# dig_ac230.net
KiCad netlist of a schematic drawn in EAGLE
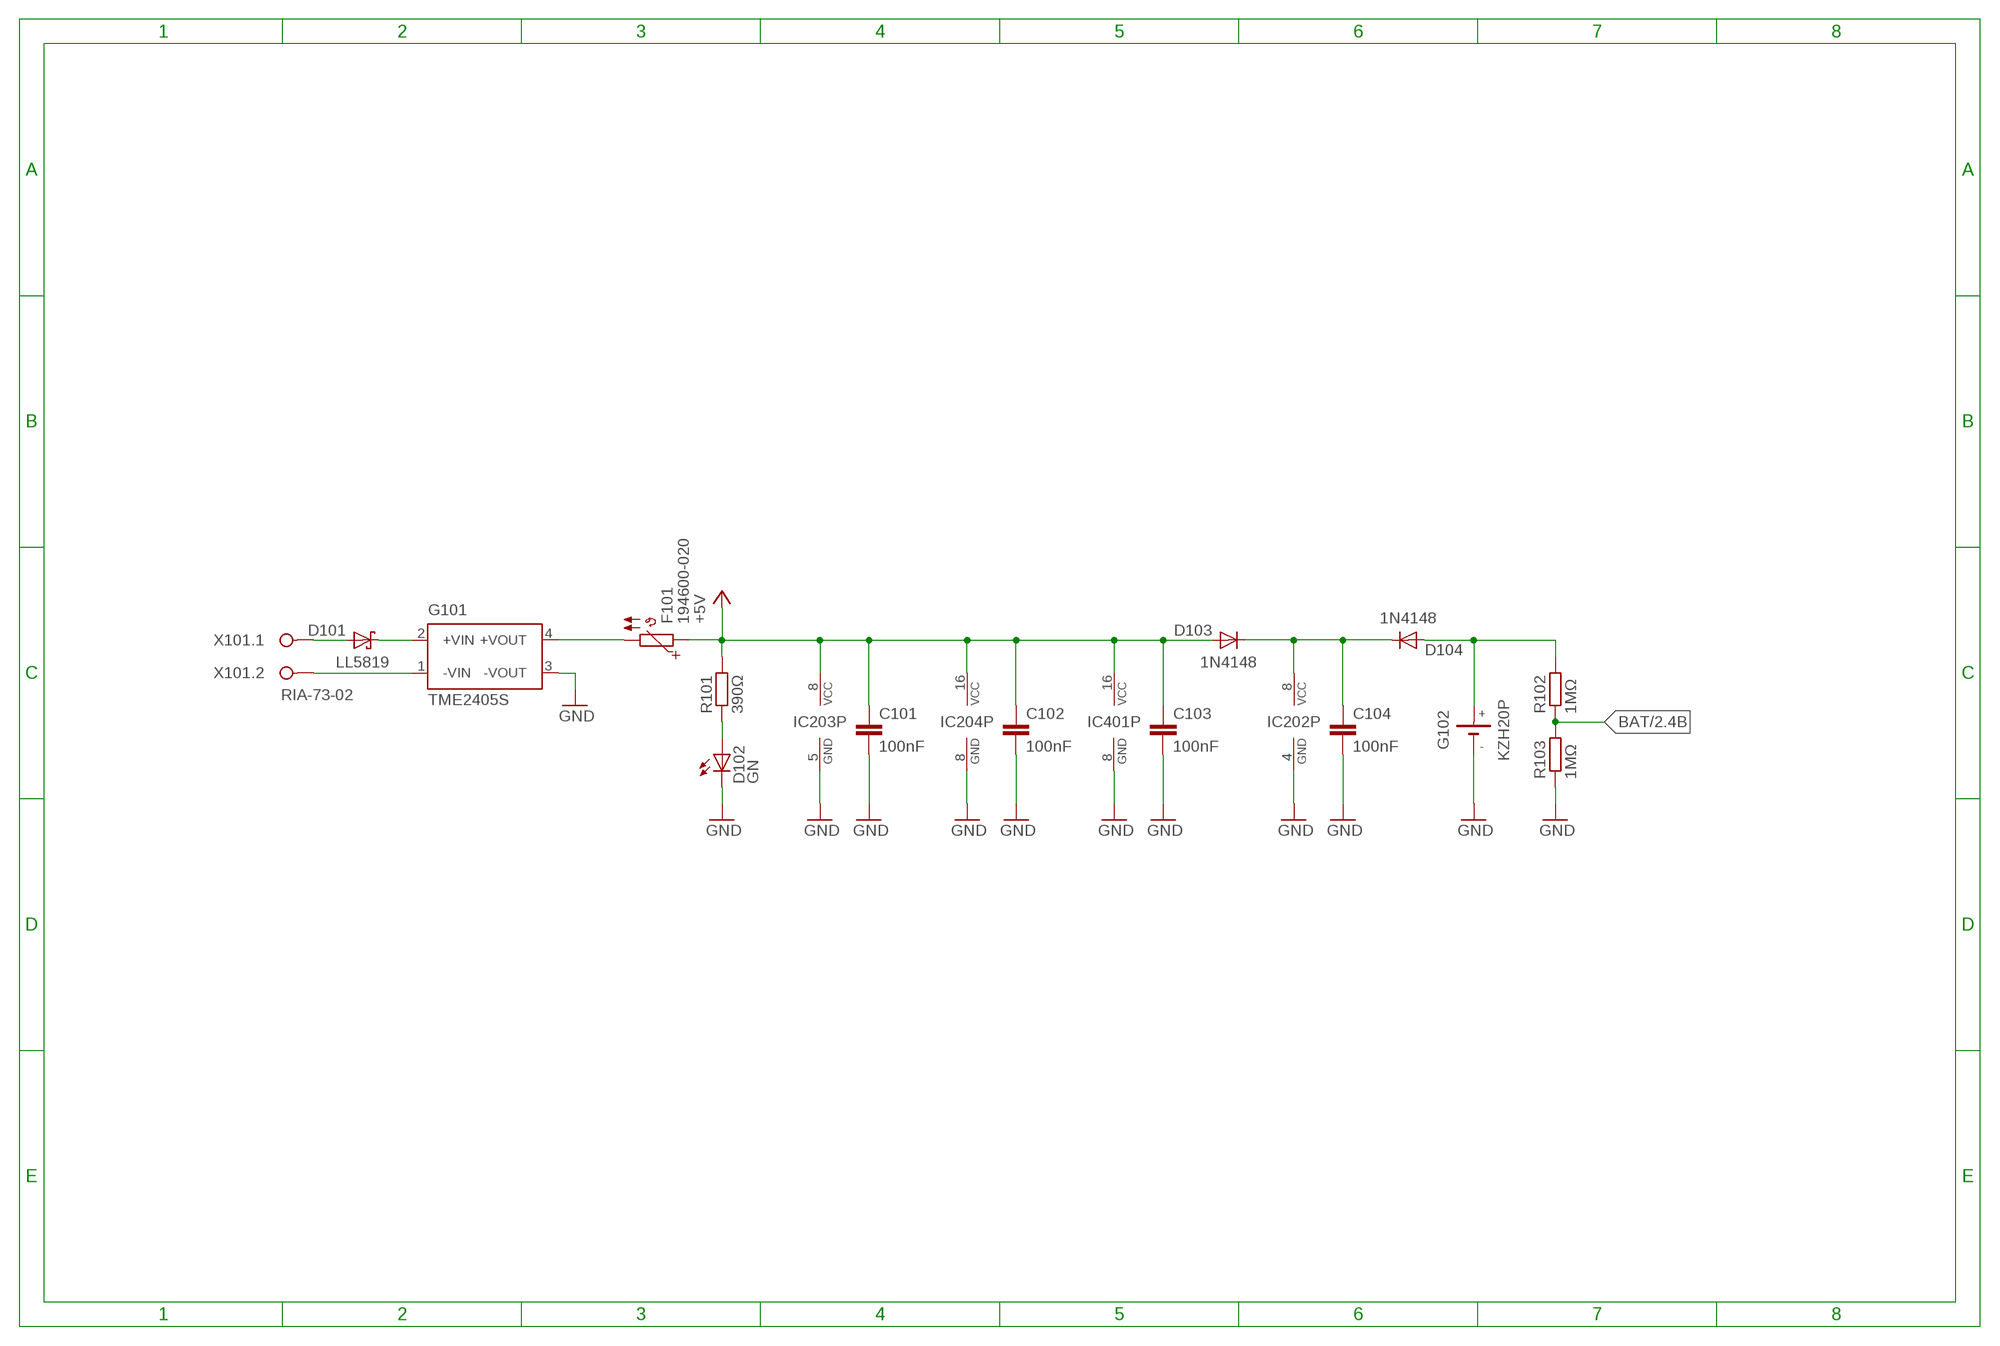
[diagram p0: schematic, sheet 1]
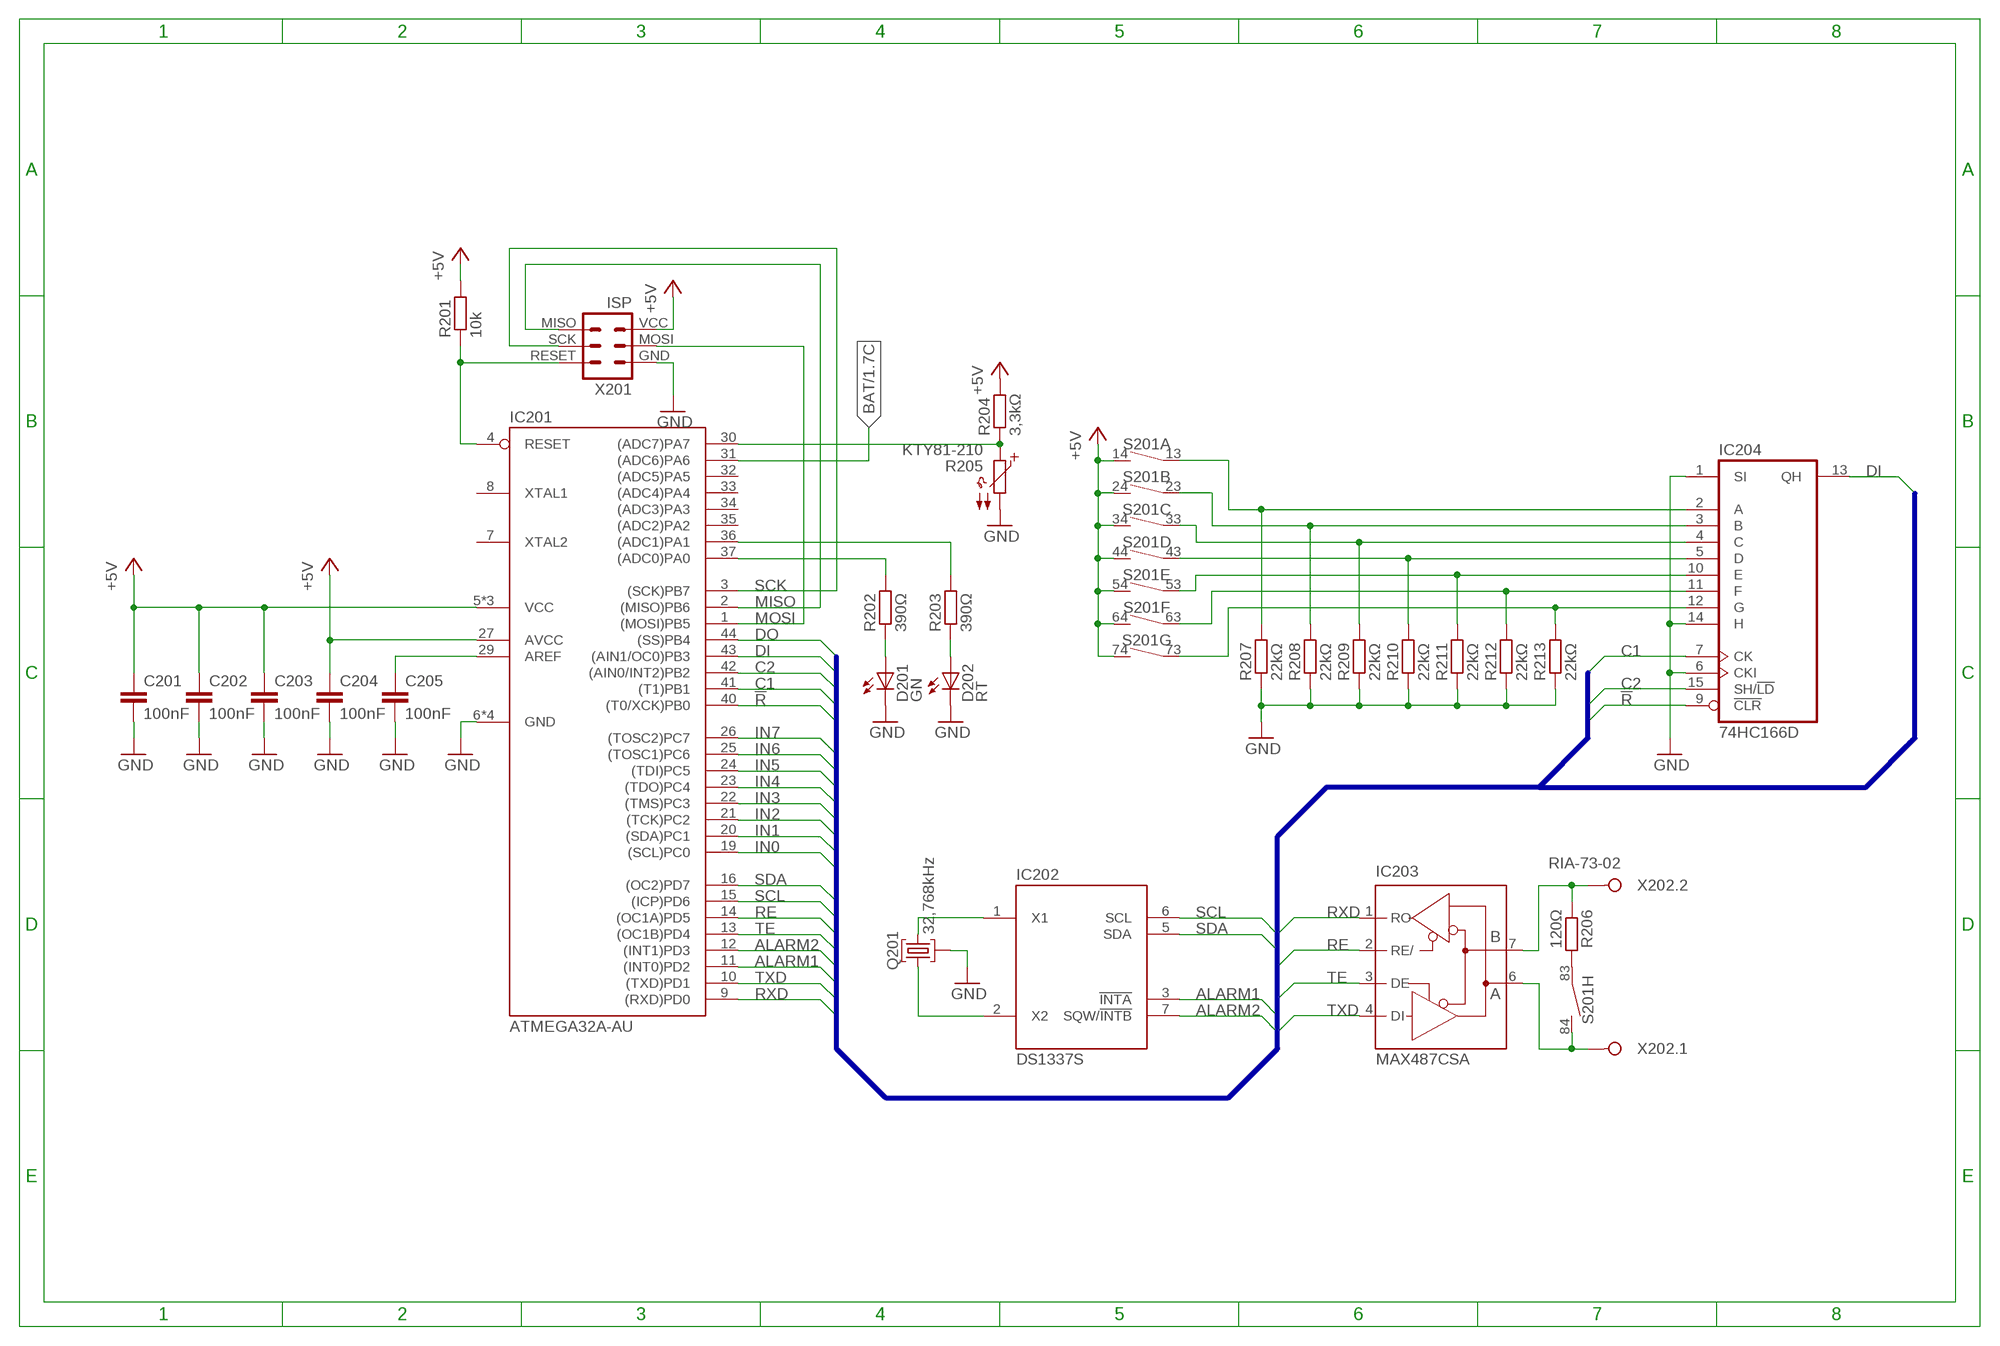
[diagram p1: schematic, sheet 2]
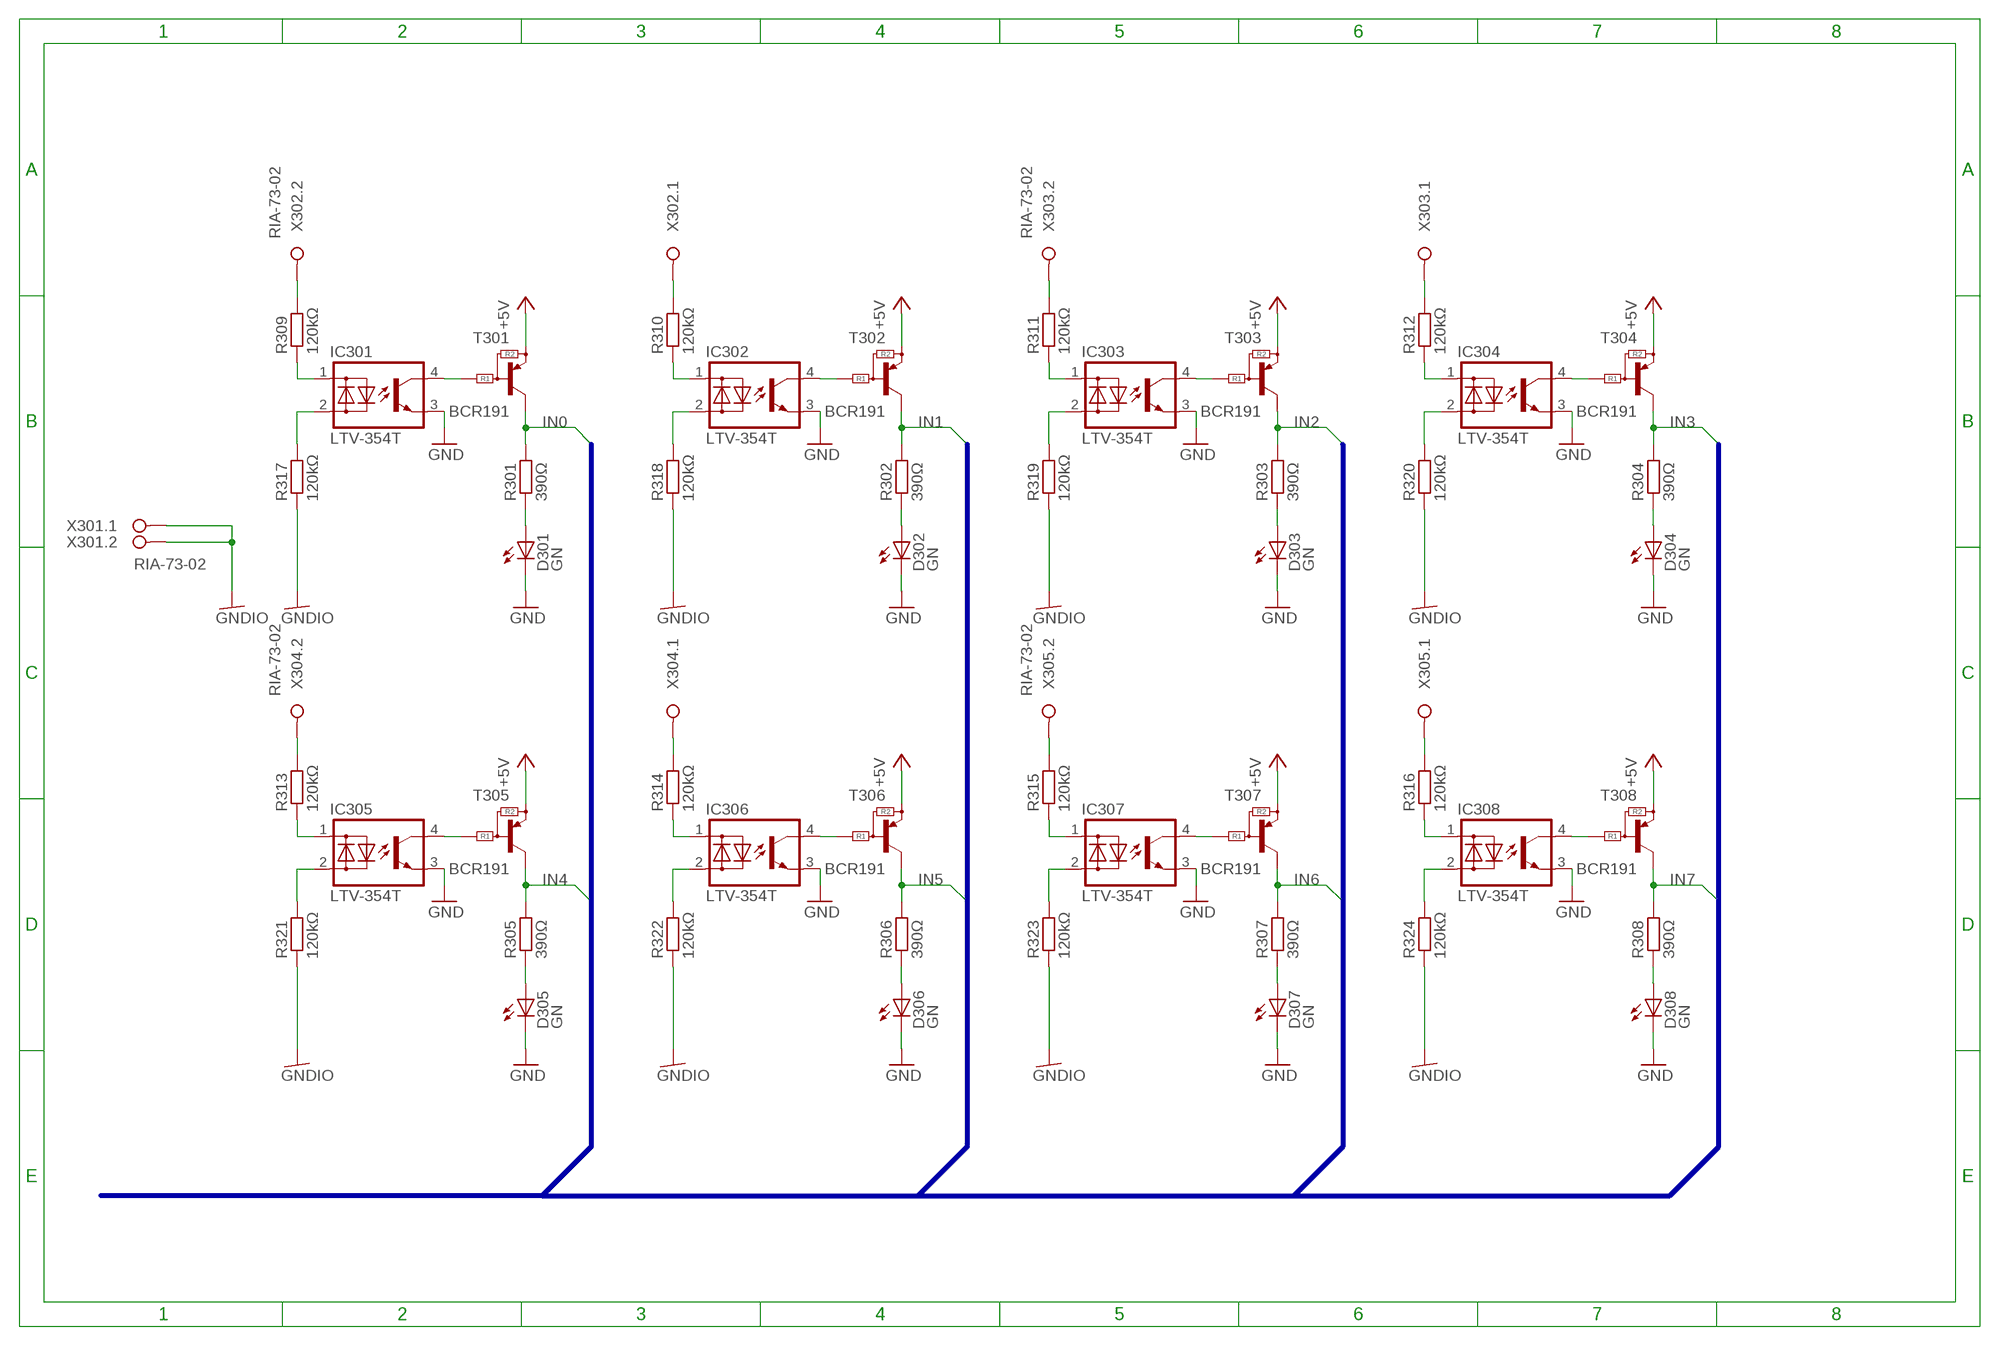
[diagram p2: schematic, sheet 3]
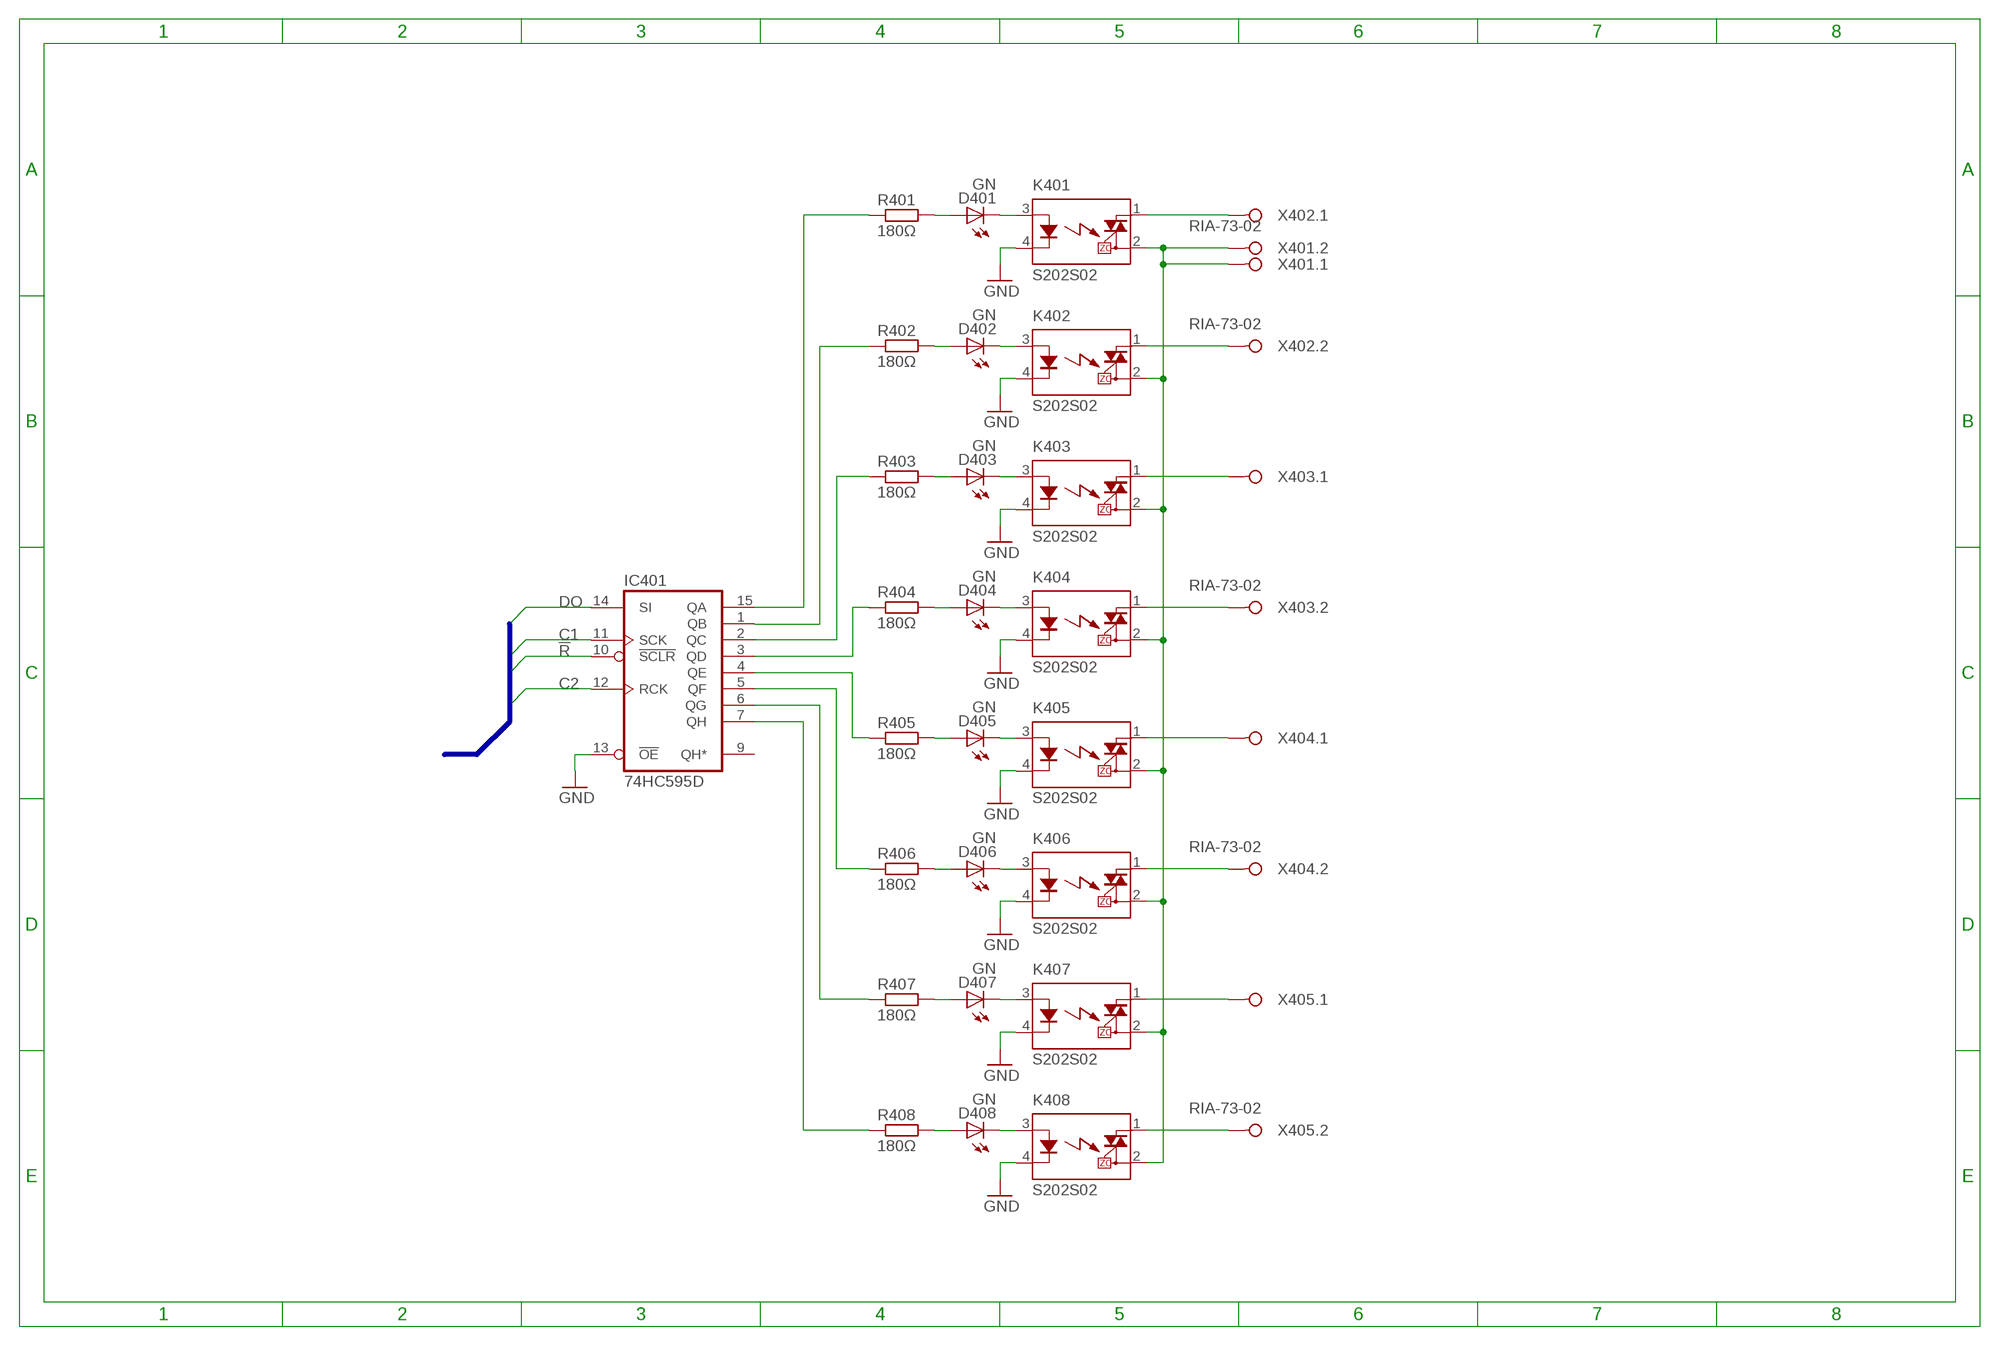
[diagram p3: schematic, sheet 4]

(export (version "E")
  (design (tool "Eeschema 10.0.6"))
  (components
    (comp (ref "D401")
      (value "GN")
      (footprint "eagle-import:LED3MM")
      (libsource (lib "eagle-import") (part "LED3MM"))
    )
    (comp (ref "D402")
      (value "GN")
      (footprint "eagle-import:LED3MM")
      (libsource (lib "eagle-import") (part "LED3MM"))
    )
    (comp (ref "D403")
      (value "GN")
      (footprint "eagle-import:LED3MM")
      (libsource (lib "eagle-import") (part "LED3MM"))
    )
    (comp (ref "D404")
      (value "GN")
      (footprint "eagle-import:LED3MM")
      (libsource (lib "eagle-import") (part "LED3MM"))
    )
    (comp (ref "D405")
      (value "GN")
      (footprint "eagle-import:LED3MM")
      (libsource (lib "eagle-import") (part "LED3MM"))
    )
    (comp (ref "D406")
      (value "GN")
      (footprint "eagle-import:LED3MM")
      (libsource (lib "eagle-import") (part "LED3MM"))
    )
    (comp (ref "D407")
      (value "GN")
      (footprint "eagle-import:LED3MM")
      (libsource (lib "eagle-import") (part "LED3MM"))
    )
    (comp (ref "D408")
      (value "GN")
      (footprint "eagle-import:LED3MM")
      (libsource (lib "eagle-import") (part "LED3MM"))
    )
    (comp (ref "IC401")
      (value "74HC595D")
      (footprint "eagle-import:SOP16_127")
      (libsource (lib "eagle-import") (part "74595DHC"))
    )
    (comp (ref "K401")
      (value "S202S02")
      (footprint "eagle-import:SIP4")
      (libsource (lib "eagle-import") (part "S02S022"))
    )
    (comp (ref "K402")
      (value "S202S02")
      (footprint "eagle-import:SIP4")
      (libsource (lib "eagle-import") (part "S02S022"))
    )
    (comp (ref "K403")
      (value "S202S02")
      (footprint "eagle-import:SIP4")
      (libsource (lib "eagle-import") (part "S02S022"))
    )
    (comp (ref "K404")
      (value "S202S02")
      (footprint "eagle-import:SIP4")
      (libsource (lib "eagle-import") (part "S02S022"))
    )
    (comp (ref "K405")
      (value "S202S02")
      (footprint "eagle-import:SIP4")
      (libsource (lib "eagle-import") (part "S02S022"))
    )
    (comp (ref "K406")
      (value "S202S02")
      (footprint "eagle-import:SIP4")
      (libsource (lib "eagle-import") (part "S02S022"))
    )
    (comp (ref "K407")
      (value "S202S02")
      (footprint "eagle-import:SIP4")
      (libsource (lib "eagle-import") (part "S02S022"))
    )
    (comp (ref "K408")
      (value "S202S02")
      (footprint "eagle-import:SIP4")
      (libsource (lib "eagle-import") (part "S02S022"))
    )
    (comp (ref "R401")
      (value "180Ω")
      (footprint "eagle-import:CHIP_0805")
      (libsource (lib "eagle-import") (part "R_0805"))
    )
    (comp (ref "R402")
      (value "180Ω")
      (footprint "eagle-import:CHIP_0805")
      (libsource (lib "eagle-import") (part "R_0805"))
    )
    (comp (ref "R403")
      (value "180Ω")
      (footprint "eagle-import:CHIP_0805")
      (libsource (lib "eagle-import") (part "R_0805"))
    )
    (comp (ref "R404")
      (value "180Ω")
      (footprint "eagle-import:CHIP_0805")
      (libsource (lib "eagle-import") (part "R_0805"))
    )
    (comp (ref "R405")
      (value "180Ω")
      (footprint "eagle-import:CHIP_0805")
      (libsource (lib "eagle-import") (part "R_0805"))
    )
    (comp (ref "R406")
      (value "180Ω")
      (footprint "eagle-import:CHIP_0805")
      (libsource (lib "eagle-import") (part "R_0805"))
    )
    (comp (ref "R407")
      (value "180Ω")
      (footprint "eagle-import:CHIP_0805")
      (libsource (lib "eagle-import") (part "R_0805"))
    )
    (comp (ref "R408")
      (value "180Ω")
      (footprint "eagle-import:CHIP_0805")
      (libsource (lib "eagle-import") (part "R_0805"))
    )
    (comp (ref "X401")
      (value "RIA-73-02")
      (footprint "eagle-import:RIA-73-02")
      (libsource (lib "eagle-import") (part "RIA-73-02"))
    )
    (comp (ref "X402")
      (value "RIA-73-02")
      (footprint "eagle-import:RIA-73-02")
      (libsource (lib "eagle-import") (part "RIA-73-02"))
    )
    (comp (ref "X403")
      (value "RIA-73-02")
      (footprint "eagle-import:RIA-73-02")
      (libsource (lib "eagle-import") (part "RIA-73-02"))
    )
    (comp (ref "X404")
      (value "RIA-73-02")
      (footprint "eagle-import:RIA-73-02")
      (libsource (lib "eagle-import") (part "RIA-73-02"))
    )
    (comp (ref "X405")
      (value "RIA-73-02")
      (footprint "eagle-import:RIA-73-02")
      (libsource (lib "eagle-import") (part "RIA-73-02"))
    )
    (comp (ref "C101")
      (value "100nF")
      (footprint "eagle-import:CHIP_0805")
      (libsource (lib "eagle-import") (part "C_0805"))
    )
    (comp (ref "C102")
      (value "100nF")
      (footprint "eagle-import:CHIP_0805")
      (libsource (lib "eagle-import") (part "C_0805"))
    )
    (comp (ref "C103")
      (value "100nF")
      (footprint "eagle-import:CHIP_0805")
      (libsource (lib "eagle-import") (part "C_0805"))
    )
    (comp (ref "C104")
      (value "100nF")
      (footprint "eagle-import:CHIP_0805")
      (libsource (lib "eagle-import") (part "C_0805"))
    )
    (comp (ref "D101")
      (value "LL5819")
      (footprint "eagle-import:MELF")
      (libsource (lib "eagle-import") (part "SHOTKY-DIODE-MELF"))
    )
    (comp (ref "D102")
      (value "GN")
      (footprint "eagle-import:LED3MM")
      (libsource (lib "eagle-import") (part "LED3MM"))
    )
    (comp (ref "D103")
      (value "1N4148")
      (footprint "eagle-import:MINIMELF")
      (libsource (lib "eagle-import") (part "DIODE-MINIMELF"))
    )
    (comp (ref "D104")
      (value "1N4148")
      (footprint "eagle-import:MINIMELF")
      (libsource (lib "eagle-import") (part "DIODE-MINIMELF"))
    )
    (comp (ref "F101")
      (value "194600-020")
      (footprint "eagle-import:CHIP_1812")
      (libsource (lib "eagle-import") (part "194600-020"))
    )
    (comp (ref "G101")
      (value "TME2405S")
      (footprint "eagle-import:TME-24V")
      (fields
        (field (name "MPN") "TME 2405S")
        (field (name "MPN_1") "TME 2405S")
        (field (name "OC_FARNELL") "1007547")
        (field (name "OC_NEWARK") "51R5329")
      )
      (libsource (lib "eagle-import") (part "TME?2405S"))
    )
    (comp (ref "G102")
      (value "KZH20P")
      (footprint "eagle-import:KZH20P")
      (libsource (lib "eagle-import") (part "KZH20P"))
    )
    (comp (ref "IC202")
      (value "DS1337S")
      (footprint "eagle-import:SOP08_127")
      (libsource (lib "eagle-import") (part "DS1337S"))
    )
    (comp (ref "IC203")
      (value "MAX487CSA")
      (footprint "eagle-import:SOP08_127")
      (libsource (lib "eagle-import") (part "MAX48CSA7"))
    )
    (comp (ref "IC204")
      (value "74HC166D")
      (footprint "eagle-import:SOP16_127")
      (libsource (lib "eagle-import") (part "74166DHC"))
    )
    (comp (ref "R101")
      (value "390Ω")
      (footprint "eagle-import:CHIP_0805")
      (libsource (lib "eagle-import") (part "R_0805"))
    )
    (comp (ref "R102")
      (value "1MΩ")
      (footprint "eagle-import:CHIP_0805")
      (libsource (lib "eagle-import") (part "R_0805"))
    )
    (comp (ref "R103")
      (value "1MΩ")
      (footprint "eagle-import:CHIP_0805")
      (libsource (lib "eagle-import") (part "R_0805"))
    )
    (comp (ref "X101")
      (value "RIA-73-02")
      (footprint "eagle-import:RIA-73-02")
      (libsource (lib "eagle-import") (part "RIA-73-02"))
    )
    (comp (ref "D301")
      (value "GN")
      (footprint "eagle-import:LED3MM")
      (libsource (lib "eagle-import") (part "LED3MM"))
    )
    (comp (ref "D302")
      (value "GN")
      (footprint "eagle-import:LED3MM")
      (libsource (lib "eagle-import") (part "LED3MM"))
    )
    (comp (ref "D303")
      (value "GN")
      (footprint "eagle-import:LED3MM")
      (libsource (lib "eagle-import") (part "LED3MM"))
    )
    (comp (ref "D304")
      (value "GN")
      (footprint "eagle-import:LED3MM")
      (libsource (lib "eagle-import") (part "LED3MM"))
    )
    (comp (ref "D305")
      (value "GN")
      (footprint "eagle-import:LED3MM")
      (libsource (lib "eagle-import") (part "LED3MM"))
    )
    (comp (ref "D306")
      (value "GN")
      (footprint "eagle-import:LED3MM")
      (libsource (lib "eagle-import") (part "LED3MM"))
    )
    (comp (ref "D307")
      (value "GN")
      (footprint "eagle-import:LED3MM")
      (libsource (lib "eagle-import") (part "LED3MM"))
    )
    (comp (ref "D308")
      (value "GN")
      (footprint "eagle-import:LED3MM")
      (libsource (lib "eagle-import") (part "LED3MM"))
    )
    (comp (ref "IC301")
      (value "LTV-354T")
      (footprint "eagle-import:SOP04_254")
      (libsource (lib "eagle-import") (part "LTV-354T"))
    )
    (comp (ref "IC302")
      (value "LTV-354T")
      (footprint "eagle-import:SOP04_254")
      (libsource (lib "eagle-import") (part "LTV-354T"))
    )
    (comp (ref "IC303")
      (value "LTV-354T")
      (footprint "eagle-import:SOP04_254")
      (libsource (lib "eagle-import") (part "LTV-354T"))
    )
    (comp (ref "IC304")
      (value "LTV-354T")
      (footprint "eagle-import:SOP04_254")
      (libsource (lib "eagle-import") (part "LTV-354T"))
    )
    (comp (ref "IC305")
      (value "LTV-354T")
      (footprint "eagle-import:SOP04_254")
      (libsource (lib "eagle-import") (part "LTV-354T"))
    )
    (comp (ref "IC306")
      (value "LTV-354T")
      (footprint "eagle-import:SOP04_254")
      (libsource (lib "eagle-import") (part "LTV-354T"))
    )
    (comp (ref "IC307")
      (value "LTV-354T")
      (footprint "eagle-import:SOP04_254")
      (libsource (lib "eagle-import") (part "LTV-354T"))
    )
    (comp (ref "IC308")
      (value "LTV-354T")
      (footprint "eagle-import:SOP04_254")
      (libsource (lib "eagle-import") (part "LTV-354T"))
    )
    (comp (ref "R301")
      (value "390Ω")
      (footprint "eagle-import:CHIP_0805")
      (libsource (lib "eagle-import") (part "R_0805"))
    )
    (comp (ref "R302")
      (value "390Ω")
      (footprint "eagle-import:CHIP_0805")
      (libsource (lib "eagle-import") (part "R_0805"))
    )
    (comp (ref "R303")
      (value "390Ω")
      (footprint "eagle-import:CHIP_0805")
      (libsource (lib "eagle-import") (part "R_0805"))
    )
    (comp (ref "R304")
      (value "390Ω")
      (footprint "eagle-import:CHIP_0805")
      (libsource (lib "eagle-import") (part "R_0805"))
    )
    (comp (ref "R305")
      (value "390Ω")
      (footprint "eagle-import:CHIP_0805")
      (libsource (lib "eagle-import") (part "R_0805"))
    )
    (comp (ref "R306")
      (value "390Ω")
      (footprint "eagle-import:CHIP_0805")
      (libsource (lib "eagle-import") (part "R_0805"))
    )
    (comp (ref "R307")
      (value "390Ω")
      (footprint "eagle-import:CHIP_0805")
      (libsource (lib "eagle-import") (part "R_0805"))
    )
    (comp (ref "R308")
      (value "390Ω")
      (footprint "eagle-import:CHIP_0805")
      (libsource (lib "eagle-import") (part "R_0805"))
    )
    (comp (ref "R309")
      (value "120kΩ")
      (footprint "eagle-import:CHIP_1206")
      (libsource (lib "eagle-import") (part "R_1206"))
    )
    (comp (ref "R310")
      (value "120kΩ")
      (footprint "eagle-import:CHIP_1206")
      (libsource (lib "eagle-import") (part "R_1206"))
    )
    (comp (ref "R311")
      (value "120kΩ")
      (footprint "eagle-import:CHIP_1206")
      (libsource (lib "eagle-import") (part "R_1206"))
    )
    (comp (ref "R312")
      (value "120kΩ")
      (footprint "eagle-import:CHIP_1206")
      (libsource (lib "eagle-import") (part "R_1206"))
    )
    (comp (ref "R313")
      (value "120kΩ")
      (footprint "eagle-import:CHIP_1206")
      (libsource (lib "eagle-import") (part "R_1206"))
    )
    (comp (ref "R314")
      (value "120kΩ")
      (footprint "eagle-import:CHIP_1206")
      (libsource (lib "eagle-import") (part "R_1206"))
    )
    (comp (ref "R315")
      (value "120kΩ")
      (footprint "eagle-import:CHIP_1206")
      (libsource (lib "eagle-import") (part "R_1206"))
    )
    (comp (ref "R316")
      (value "120kΩ")
      (footprint "eagle-import:CHIP_1206")
      (libsource (lib "eagle-import") (part "R_1206"))
    )
    (comp (ref "R317")
      (value "120kΩ")
      (footprint "eagle-import:CHIP_1206")
      (libsource (lib "eagle-import") (part "R_1206"))
    )
    (comp (ref "R318")
      (value "120kΩ")
      (footprint "eagle-import:CHIP_1206")
      (libsource (lib "eagle-import") (part "R_1206"))
    )
    (comp (ref "R319")
      (value "120kΩ")
      (footprint "eagle-import:CHIP_1206")
      (libsource (lib "eagle-import") (part "R_1206"))
    )
    (comp (ref "R320")
      (value "120kΩ")
      (footprint "eagle-import:CHIP_1206")
      (libsource (lib "eagle-import") (part "R_1206"))
    )
    (comp (ref "R321")
      (value "120kΩ")
      (footprint "eagle-import:CHIP_1206")
      (libsource (lib "eagle-import") (part "R_1206"))
    )
    (comp (ref "R322")
      (value "120kΩ")
      (footprint "eagle-import:CHIP_1206")
      (libsource (lib "eagle-import") (part "R_1206"))
    )
    (comp (ref "R323")
      (value "120kΩ")
      (footprint "eagle-import:CHIP_1206")
      (libsource (lib "eagle-import") (part "R_1206"))
    )
    (comp (ref "R324")
      (value "120kΩ")
      (footprint "eagle-import:CHIP_1206")
      (libsource (lib "eagle-import") (part "R_1206"))
    )
    (comp (ref "T301")
      (value "BCR191")
      (footprint "eagle-import:SOT23")
      (libsource (lib "eagle-import") (part "PNP2R-SOT23-BEC"))
    )
    (comp (ref "T302")
      (value "BCR191")
      (footprint "eagle-import:SOT23")
      (libsource (lib "eagle-import") (part "PNP2R-SOT23-BEC"))
    )
    (comp (ref "T303")
      (value "BCR191")
      (footprint "eagle-import:SOT23")
      (libsource (lib "eagle-import") (part "PNP2R-SOT23-BEC"))
    )
    (comp (ref "T304")
      (value "BCR191")
      (footprint "eagle-import:SOT23")
      (libsource (lib "eagle-import") (part "PNP2R-SOT23-BEC"))
    )
    (comp (ref "T305")
      (value "BCR191")
      (footprint "eagle-import:SOT23")
      (libsource (lib "eagle-import") (part "PNP2R-SOT23-BEC"))
    )
    (comp (ref "T306")
      (value "BCR191")
      (footprint "eagle-import:SOT23")
      (libsource (lib "eagle-import") (part "PNP2R-SOT23-BEC"))
    )
    (comp (ref "T307")
      (value "BCR191")
      (footprint "eagle-import:SOT23")
      (libsource (lib "eagle-import") (part "PNP2R-SOT23-BEC"))
    )
    (comp (ref "T308")
      (value "BCR191")
      (footprint "eagle-import:SOT23")
      (libsource (lib "eagle-import") (part "PNP2R-SOT23-BEC"))
    )
    (comp (ref "X301")
      (value "RIA-73-02")
      (footprint "eagle-import:RIA-73-02")
      (libsource (lib "eagle-import") (part "RIA-73-02"))
    )
    (comp (ref "X302")
      (value "RIA-73-02")
      (footprint "eagle-import:RIA-73-02")
      (libsource (lib "eagle-import") (part "RIA-73-02"))
    )
    (comp (ref "X303")
      (value "RIA-73-02")
      (footprint "eagle-import:RIA-73-02")
      (libsource (lib "eagle-import") (part "RIA-73-02"))
    )
    (comp (ref "X304")
      (value "RIA-73-02")
      (footprint "eagle-import:RIA-73-02")
      (libsource (lib "eagle-import") (part "RIA-73-02"))
    )
    (comp (ref "X305")
      (value "RIA-73-02")
      (footprint "eagle-import:RIA-73-02")
      (libsource (lib "eagle-import") (part "RIA-73-02"))
    )
    (comp (ref "C201")
      (value "100nF")
      (footprint "eagle-import:CHIP_0805")
      (libsource (lib "eagle-import") (part "C_0805"))
    )
    (comp (ref "C202")
      (value "100nF")
      (footprint "eagle-import:CHIP_0805")
      (libsource (lib "eagle-import") (part "C_0805"))
    )
    (comp (ref "C203")
      (value "100nF")
      (footprint "eagle-import:CHIP_0805")
      (libsource (lib "eagle-import") (part "C_0805"))
    )
    (comp (ref "C204")
      (value "100nF")
      (footprint "eagle-import:CHIP_0805")
      (libsource (lib "eagle-import") (part "C_0805"))
    )
    (comp (ref "C205")
      (value "100nF")
      (footprint "eagle-import:CHIP_0805")
      (libsource (lib "eagle-import") (part "C_0805"))
    )
    (comp (ref "D201")
      (value "GN")
      (footprint "eagle-import:LED3MM")
      (libsource (lib "eagle-import") (part "LED3MM"))
    )
    (comp (ref "D202")
      (value "RT")
      (footprint "eagle-import:LED3MM")
      (libsource (lib "eagle-import") (part "LED3MM"))
    )
    (comp (ref "IC201")
      (value "ATMEGA32A-AU")
      (footprint "eagle-import:QFP44_08")
      (libsource (lib "eagle-import") (part "ATMEGA32A-AU"))
    )
    (comp (ref "Q201")
      (value "32,768kHz")
      (footprint "eagle-import:MS1V-T1K")
      (libsource (lib "eagle-import") (part "QM_"))
    )
    (comp (ref "R201")
      (value "10k")
      (footprint "eagle-import:CHIP_0805")
      (libsource (lib "eagle-import") (part "R_0805"))
    )
    (comp (ref "R202")
      (value "390Ω")
      (footprint "eagle-import:CHIP_0805")
      (libsource (lib "eagle-import") (part "R_0805"))
    )
    (comp (ref "R203")
      (value "390Ω")
      (footprint "eagle-import:CHIP_0805")
      (libsource (lib "eagle-import") (part "R_0805"))
    )
    (comp (ref "R204")
      (value "3,3kΩ")
      (footprint "eagle-import:CHIP_0805")
      (libsource (lib "eagle-import") (part "R_0805"))
    )
    (comp (ref "R205")
      (value "KTY81-210")
      (footprint "eagle-import:TO92")
      (libsource (lib "eagle-import") (part "KTY81-210"))
    )
    (comp (ref "R206")
      (value "120Ω")
      (footprint "eagle-import:CHIP_0805")
      (libsource (lib "eagle-import") (part "R_0805"))
    )
    (comp (ref "R207")
      (value "22kΩ")
      (footprint "eagle-import:CHIP_0805")
      (libsource (lib "eagle-import") (part "R_0805"))
    )
    (comp (ref "R208")
      (value "22kΩ")
      (footprint "eagle-import:CHIP_0805")
      (libsource (lib "eagle-import") (part "R_0805"))
    )
    (comp (ref "R209")
      (value "22kΩ")
      (footprint "eagle-import:CHIP_0805")
      (libsource (lib "eagle-import") (part "R_0805"))
    )
    (comp (ref "R210")
      (value "22kΩ")
      (footprint "eagle-import:CHIP_0805")
      (libsource (lib "eagle-import") (part "R_0805"))
    )
    (comp (ref "R211")
      (value "22kΩ")
      (footprint "eagle-import:CHIP_0805")
      (libsource (lib "eagle-import") (part "R_0805"))
    )
    (comp (ref "R212")
      (value "22kΩ")
      (footprint "eagle-import:CHIP_0805")
      (libsource (lib "eagle-import") (part "R_0805"))
    )
    (comp (ref "R213")
      (value "22kΩ")
      (footprint "eagle-import:CHIP_0805")
      (libsource (lib "eagle-import") (part "R_0805"))
    )
    (comp (ref "S201")
      (value "DP08")
      (footprint "eagle-import:DP08")
      (libsource (lib "eagle-import") (part "DP08"))
    )
    (comp (ref "X201")
      (value "ISP")
      (footprint "eagle-import:ML6L")
      (libsource (lib "eagle-import") (part "AVR_ISP6L"))
    )
    (comp (ref "X202")
      (value "RIA-73-02")
      (footprint "eagle-import:RIA-73-02")
      (libsource (lib "eagle-import") (part "RIA-73-02"))
    )
  )
  (nets
    (net (code "1") (name "+5V") (class "Default")
      (node (ref "C101") (pin "1") (pinfunction "1_1") (pintype "passive"))
      (node (ref "C102") (pin "1") (pinfunction "1_1") (pintype "passive"))
      (node (ref "C103") (pin "1") (pinfunction "1_1") (pintype "passive"))
      (node (ref "C201") (pin "1") (pinfunction "1_1") (pintype "passive"))
      (node (ref "C202") (pin "1") (pinfunction "1_1") (pintype "passive"))
      (node (ref "C203") (pin "1") (pinfunction "1_1") (pintype "passive"))
      (node (ref "C204") (pin "1") (pinfunction "1_1") (pintype "passive"))
      (node (ref "D103") (pin "A") (pinfunction "A_A") (pintype "passive"))
      (node (ref "F101") (pin "1") (pinfunction "1_1") (pintype "passive"))
      (node (ref "IC201") (pin "17") (pinfunction "VCC_17") (pintype "power_in"))
      (node (ref "IC201") (pin "27") (pinfunction "AVCC_27") (pintype "power_in"))
      (node (ref "IC201") (pin "38") (pinfunction "VCC_38") (pintype "power_in"))
      (node (ref "IC201") (pin "5") (pinfunction "VCC_5") (pintype "power_in"))
      (node (ref "IC203") (pin "8") (pinfunction "VCC_8") (pintype "power_in"))
      (node (ref "IC204") (pin "16") (pinfunction "VCC_16") (pintype "power_in"))
      (node (ref "IC401") (pin "16") (pinfunction "VCC_16") (pintype "power_in"))
      (node (ref "R101") (pin "2") (pinfunction "2_2") (pintype "passive"))
      (node (ref "R201") (pin "2") (pinfunction "2_2") (pintype "passive"))
      (node (ref "R204") (pin "2") (pinfunction "2_2") (pintype "passive"))
      (node (ref "S201") (pin "14") (pinfunction "4_14") (pintype "passive"))
      (node (ref "S201") (pin "24") (pinfunction "4_24") (pintype "passive"))
      (node (ref "S201") (pin "34") (pinfunction "4_34") (pintype "passive"))
      (node (ref "S201") (pin "44") (pinfunction "4_44") (pintype "passive"))
      (node (ref "S201") (pin "54") (pinfunction "4_54") (pintype "passive"))
      (node (ref "S201") (pin "64") (pinfunction "4_64") (pintype "passive"))
      (node (ref "S201") (pin "74") (pinfunction "4_74") (pintype "passive"))
      (node (ref "T301") (pin "2") (pinfunction "E_2") (pintype "passive"))
      (node (ref "T302") (pin "2") (pinfunction "E_2") (pintype "passive"))
      (node (ref "T303") (pin "2") (pinfunction "E_2") (pintype "passive"))
      (node (ref "T304") (pin "2") (pinfunction "E_2") (pintype "passive"))
      (node (ref "T305") (pin "2") (pinfunction "E_2") (pintype "passive"))
      (node (ref "T306") (pin "2") (pinfunction "E_2") (pintype "passive"))
      (node (ref "T307") (pin "2") (pinfunction "E_2") (pintype "passive"))
      (node (ref "T308") (pin "2") (pinfunction "E_2") (pintype "passive"))
      (node (ref "X201") (pin "VCC") (pinfunction "VCC_VCC") (pintype "passive"))
    )
    (net (code "2") (name "ALARM1") (class "Default")
      (node (ref "IC201") (pin "11") (pinfunction "(INT0)PD2_11") (pintype "bidirectional"))
      (node (ref "IC202") (pin "3") (pinfunction "~{INTA}_3") (pintype "open_collector"))
    )
    (net (code "3") (name "ALARM2") (class "Default")
      (node (ref "IC201") (pin "12") (pinfunction "(INT1)PD3_12") (pintype "bidirectional"))
      (node (ref "IC202") (pin "7") (pinfunction "SQW/~{INTB}_7") (pintype "open_collector"))
    )
    (net (code "4") (name "BAT") (class "Default")
      (node (ref "IC201") (pin "31") (pinfunction "(ADC6)PA6_31") (pintype "bidirectional"))
      (node (ref "R102") (pin "1") (pinfunction "1_1") (pintype "passive"))
      (node (ref "R103") (pin "2") (pinfunction "2_2") (pintype "passive"))
    )
    (net (code "5") (name "C1") (class "Default")
      (node (ref "IC201") (pin "41") (pinfunction "(T1)PB1_41") (pintype "bidirectional"))
      (node (ref "IC204") (pin "7") (pinfunction "CK_7") (pintype "input"))
      (node (ref "IC401") (pin "11") (pinfunction "SCK_11") (pintype "input"))
    )
    (net (code "6") (name "C2") (class "Default")
      (node (ref "IC201") (pin "42") (pinfunction "(AIN0/INT2)PB2_42") (pintype "bidirectional"))
      (node (ref "IC204") (pin "15") (pinfunction "SH/~{LD}_15") (pintype "input"))
      (node (ref "IC401") (pin "12") (pinfunction "RCK_12") (pintype "input"))
    )
    (net (code "7") (name "DI") (class "Default")
      (node (ref "IC201") (pin "43") (pinfunction "(AIN1/OC0)PB3_43") (pintype "bidirectional"))
      (node (ref "IC204") (pin "13") (pinfunction "QH_13") (pintype "output"))
    )
    (net (code "8") (name "DO") (class "Default")
      (node (ref "IC201") (pin "44") (pinfunction "(SS)PB4_44") (pintype "bidirectional"))
      (node (ref "IC401") (pin "14") (pinfunction "SI_14") (pintype "input"))
    )
    (net (code "9") (name "GND") (class "Default")
      (node (ref "C101") (pin "2") (pinfunction "2_2") (pintype "passive"))
      (node (ref "C102") (pin "2") (pinfunction "2_2") (pintype "passive"))
      (node (ref "C103") (pin "2") (pinfunction "2_2") (pintype "passive"))
      (node (ref "C104") (pin "2") (pinfunction "2_2") (pintype "passive"))
      (node (ref "C201") (pin "2") (pinfunction "2_2") (pintype "passive"))
      (node (ref "C202") (pin "2") (pinfunction "2_2") (pintype "passive"))
      (node (ref "C203") (pin "2") (pinfunction "2_2") (pintype "passive"))
      (node (ref "C204") (pin "2") (pinfunction "2_2") (pintype "passive"))
      (node (ref "C205") (pin "2") (pinfunction "2_2") (pintype "passive"))
      (node (ref "D102") (pin "K") (pinfunction "C_K") (pintype "passive"))
      (node (ref "D201") (pin "K") (pinfunction "C_K") (pintype "passive"))
      (node (ref "D202") (pin "K") (pinfunction "C_K") (pintype "passive"))
      (node (ref "D301") (pin "K") (pinfunction "C_K") (pintype "passive"))
      (node (ref "D302") (pin "K") (pinfunction "C_K") (pintype "passive"))
      (node (ref "D303") (pin "K") (pinfunction "C_K") (pintype "passive"))
      (node (ref "D304") (pin "K") (pinfunction "C_K") (pintype "passive"))
      (node (ref "D305") (pin "K") (pinfunction "C_K") (pintype "passive"))
      (node (ref "D306") (pin "K") (pinfunction "C_K") (pintype "passive"))
      (node (ref "D307") (pin "K") (pinfunction "C_K") (pintype "passive"))
      (node (ref "D308") (pin "K") (pinfunction "C_K") (pintype "passive"))
      (node (ref "G101") (pin "3") (pinfunction "-VOUT_3") (pintype "passive"))
      (node (ref "G102") (pin "N") (pinfunction "-_N") (pintype "passive"))
      (node (ref "IC201") (pin "18") (pinfunction "GND_18") (pintype "power_in"))
      (node (ref "IC201") (pin "28") (pinfunction "GND_28") (pintype "power_in"))
      (node (ref "IC201") (pin "39") (pinfunction "GND_39") (pintype "power_in"))
      (node (ref "IC201") (pin "6") (pinfunction "GND_6") (pintype "power_in"))
      (node (ref "IC202") (pin "4") (pinfunction "GND_4") (pintype "power_in"))
      (node (ref "IC203") (pin "5") (pinfunction "GND_5") (pintype "power_in"))
      (node (ref "IC204") (pin "1") (pinfunction "SI_1") (pintype "input"))
      (node (ref "IC204") (pin "14") (pinfunction "H_14") (pintype "input"))
      (node (ref "IC204") (pin "6") (pinfunction "CKI_6") (pintype "input"))
      (node (ref "IC204") (pin "8") (pinfunction "GND_8") (pintype "power_in"))
      (node (ref "IC301") (pin "3") (pinfunction "E_3") (pintype "passive"))
      (node (ref "IC302") (pin "3") (pinfunction "E_3") (pintype "passive"))
      (node (ref "IC303") (pin "3") (pinfunction "E_3") (pintype "passive"))
      (node (ref "IC304") (pin "3") (pinfunction "E_3") (pintype "passive"))
      (node (ref "IC305") (pin "3") (pinfunction "E_3") (pintype "passive"))
      (node (ref "IC306") (pin "3") (pinfunction "E_3") (pintype "passive"))
      (node (ref "IC307") (pin "3") (pinfunction "E_3") (pintype "passive"))
      (node (ref "IC308") (pin "3") (pinfunction "E_3") (pintype "passive"))
      (node (ref "IC401") (pin "13") (pinfunction "~{OE}_13") (pintype "input"))
      (node (ref "IC401") (pin "8") (pinfunction "GND_8") (pintype "power_in"))
      (node (ref "K401") (pin "4") (pinfunction "K_4") (pintype "passive"))
      (node (ref "K402") (pin "4") (pinfunction "K_4") (pintype "passive"))
      (node (ref "K403") (pin "4") (pinfunction "K_4") (pintype "passive"))
      (node (ref "K404") (pin "4") (pinfunction "K_4") (pintype "passive"))
      (node (ref "K405") (pin "4") (pinfunction "K_4") (pintype "passive"))
      (node (ref "K406") (pin "4") (pinfunction "K_4") (pintype "passive"))
      (node (ref "K407") (pin "4") (pinfunction "K_4") (pintype "passive"))
      (node (ref "K408") (pin "4") (pinfunction "K_4") (pintype "passive"))
      (node (ref "Q201") (pin "G") (pinfunction "G_G") (pintype "passive"))
      (node (ref "R103") (pin "1") (pinfunction "1_1") (pintype "passive"))
      (node (ref "R205") (pin "2") (pinfunction "2_2") (pintype "passive"))
      (node (ref "R207") (pin "1") (pinfunction "1_1") (pintype "passive"))
      (node (ref "R208") (pin "1") (pinfunction "1_1") (pintype "passive"))
      (node (ref "R209") (pin "1") (pinfunction "1_1") (pintype "passive"))
      (node (ref "R210") (pin "1") (pinfunction "1_1") (pintype "passive"))
      (node (ref "R211") (pin "1") (pinfunction "1_1") (pintype "passive"))
      (node (ref "R212") (pin "1") (pinfunction "1_1") (pintype "passive"))
      (node (ref "R213") (pin "1") (pinfunction "1_1") (pintype "passive"))
      (node (ref "X201") (pin "GND") (pinfunction "GND_GND") (pintype "passive"))
    )
    (net (code "10") (name "GNDIO") (class "Default")
      (node (ref "R317") (pin "1") (pinfunction "1_1") (pintype "passive"))
      (node (ref "R318") (pin "1") (pinfunction "1_1") (pintype "passive"))
      (node (ref "R319") (pin "1") (pinfunction "1_1") (pintype "passive"))
      (node (ref "R320") (pin "1") (pinfunction "1_1") (pintype "passive"))
      (node (ref "R321") (pin "1") (pinfunction "1_1") (pintype "passive"))
      (node (ref "R322") (pin "1") (pinfunction "1_1") (pintype "passive"))
      (node (ref "R323") (pin "1") (pinfunction "1_1") (pintype "passive"))
      (node (ref "R324") (pin "1") (pinfunction "1_1") (pintype "passive"))
      (node (ref "X301") (pin "1") (pinfunction "A_1") (pintype "passive"))
      (node (ref "X301") (pin "2") (pinfunction "A_2") (pintype "passive"))
    )
    (net (code "11") (name "IN0") (class "Default")
      (node (ref "IC201") (pin "19") (pinfunction "(SCL)PC0_19") (pintype "bidirectional"))
      (node (ref "R301") (pin "2") (pinfunction "2_2") (pintype "passive"))
      (node (ref "T301") (pin "3") (pinfunction "C_3") (pintype "passive"))
    )
    (net (code "12") (name "IN1") (class "Default")
      (node (ref "IC201") (pin "20") (pinfunction "(SDA)PC1_20") (pintype "bidirectional"))
      (node (ref "R302") (pin "2") (pinfunction "2_2") (pintype "passive"))
      (node (ref "T302") (pin "3") (pinfunction "C_3") (pintype "passive"))
    )
    (net (code "13") (name "IN2") (class "Default")
      (node (ref "IC201") (pin "21") (pinfunction "(TCK)PC2_21") (pintype "bidirectional"))
      (node (ref "R303") (pin "2") (pinfunction "2_2") (pintype "passive"))
      (node (ref "T303") (pin "3") (pinfunction "C_3") (pintype "passive"))
    )
    (net (code "14") (name "IN3") (class "Default")
      (node (ref "IC201") (pin "22") (pinfunction "(TMS)PC3_22") (pintype "bidirectional"))
      (node (ref "R304") (pin "2") (pinfunction "2_2") (pintype "passive"))
      (node (ref "T304") (pin "3") (pinfunction "C_3") (pintype "passive"))
    )
    (net (code "15") (name "IN4") (class "Default")
      (node (ref "IC201") (pin "23") (pinfunction "(TDO)PC4_23") (pintype "bidirectional"))
      (node (ref "R305") (pin "2") (pinfunction "2_2") (pintype "passive"))
      (node (ref "T305") (pin "3") (pinfunction "C_3") (pintype "passive"))
    )
    (net (code "16") (name "IN5") (class "Default")
      (node (ref "IC201") (pin "24") (pinfunction "(TDI)PC5_24") (pintype "bidirectional"))
      (node (ref "R306") (pin "2") (pinfunction "2_2") (pintype "passive"))
      (node (ref "T306") (pin "3") (pinfunction "C_3") (pintype "passive"))
    )
    (net (code "17") (name "IN6") (class "Default")
      (node (ref "IC201") (pin "25") (pinfunction "(TOSC1)PC6_25") (pintype "bidirectional"))
      (node (ref "R307") (pin "2") (pinfunction "2_2") (pintype "passive"))
      (node (ref "T307") (pin "3") (pinfunction "C_3") (pintype "passive"))
    )
    (net (code "18") (name "IN7") (class "Default")
      (node (ref "IC201") (pin "26") (pinfunction "(TOSC2)PC7_26") (pintype "bidirectional"))
      (node (ref "R308") (pin "2") (pinfunction "2_2") (pintype "passive"))
      (node (ref "T308") (pin "3") (pinfunction "C_3") (pintype "passive"))
    )
    (net (code "19") (name "MISO") (class "Default")
      (node (ref "IC201") (pin "2") (pinfunction "(MISO)PB6_2") (pintype "bidirectional"))
      (node (ref "X201") (pin "MISO") (pinfunction "MISO_MISO") (pintype "passive"))
    )
    (net (code "20") (name "MOSI") (class "Default")
      (node (ref "IC201") (pin "1") (pinfunction "(MOSI)PB5_1") (pintype "bidirectional"))
      (node (ref "X201") (pin "MOSI") (pinfunction "MOSI_MOSI") (pintype "passive"))
    )
    (net (code "21") (name "Net-(D102-PadA)") (class "Default")
      (node (ref "D102") (pin "A") (pinfunction "A_A") (pintype "passive"))
      (node (ref "R101") (pin "1") (pinfunction "1_1") (pintype "passive"))
    )
    (net (code "22") (name "Net-(D104-PadA)") (class "Default")
      (node (ref "D104") (pin "A") (pinfunction "A_A") (pintype "passive"))
      (node (ref "G102") (pin "P1") (pinfunction "+_P1") (pintype "passive"))
      (node (ref "G102") (pin "P2") (pinfunction "+_P2") (pintype "passive"))
      (node (ref "R102") (pin "2") (pinfunction "2_2") (pintype "passive"))
    )
    (net (code "23") (name "Net-(D201-PadA)") (class "Default")
      (node (ref "D201") (pin "A") (pinfunction "A_A") (pintype "passive"))
      (node (ref "R202") (pin "1") (pinfunction "1_1") (pintype "passive"))
    )
    (net (code "24") (name "Net-(D202-PadA)") (class "Default")
      (node (ref "D202") (pin "A") (pinfunction "A_A") (pintype "passive"))
      (node (ref "R203") (pin "1") (pinfunction "1_1") (pintype "passive"))
    )
    (net (code "25") (name "Net-(D301-PadA)") (class "Default")
      (node (ref "D301") (pin "A") (pinfunction "A_A") (pintype "passive"))
      (node (ref "R301") (pin "1") (pinfunction "1_1") (pintype "passive"))
    )
    (net (code "26") (name "Net-(D302-PadA)") (class "Default")
      (node (ref "D302") (pin "A") (pinfunction "A_A") (pintype "passive"))
      (node (ref "R302") (pin "1") (pinfunction "1_1") (pintype "passive"))
    )
    (net (code "27") (name "Net-(D303-PadA)") (class "Default")
      (node (ref "D303") (pin "A") (pinfunction "A_A") (pintype "passive"))
      (node (ref "R303") (pin "1") (pinfunction "1_1") (pintype "passive"))
    )
    (net (code "28") (name "Net-(D304-PadA)") (class "Default")
      (node (ref "D304") (pin "A") (pinfunction "A_A") (pintype "passive"))
      (node (ref "R304") (pin "1") (pinfunction "1_1") (pintype "passive"))
    )
    (net (code "29") (name "Net-(D305-PadA)") (class "Default")
      (node (ref "D305") (pin "A") (pinfunction "A_A") (pintype "passive"))
      (node (ref "R305") (pin "1") (pinfunction "1_1") (pintype "passive"))
    )
    (net (code "30") (name "Net-(D306-PadA)") (class "Default")
      (node (ref "D306") (pin "A") (pinfunction "A_A") (pintype "passive"))
      (node (ref "R306") (pin "1") (pinfunction "1_1") (pintype "passive"))
    )
    (net (code "31") (name "Net-(D307-PadA)") (class "Default")
      (node (ref "D307") (pin "A") (pinfunction "A_A") (pintype "passive"))
      (node (ref "R307") (pin "1") (pinfunction "1_1") (pintype "passive"))
    )
    (net (code "32") (name "Net-(D308-PadA)") (class "Default")
      (node (ref "D308") (pin "A") (pinfunction "A_A") (pintype "passive"))
      (node (ref "R308") (pin "1") (pinfunction "1_1") (pintype "passive"))
    )
    (net (code "33") (name "Net-(D401-C)") (class "Default")
      (node (ref "D401") (pin "K") (pinfunction "C_K") (pintype "passive"))
      (node (ref "K401") (pin "3") (pinfunction "A_3") (pintype "passive"))
    )
    (net (code "34") (name "Net-(D401-PadA)") (class "Default")
      (node (ref "D401") (pin "A") (pinfunction "A_A") (pintype "passive"))
      (node (ref "R401") (pin "2") (pinfunction "2_2") (pintype "passive"))
    )
    (net (code "35") (name "Net-(D402-C)") (class "Default")
      (node (ref "D402") (pin "K") (pinfunction "C_K") (pintype "passive"))
      (node (ref "K402") (pin "3") (pinfunction "A_3") (pintype "passive"))
    )
    (net (code "36") (name "Net-(D402-PadA)") (class "Default")
      (node (ref "D402") (pin "A") (pinfunction "A_A") (pintype "passive"))
      (node (ref "R402") (pin "2") (pinfunction "2_2") (pintype "passive"))
    )
    (net (code "37") (name "Net-(D403-C)") (class "Default")
      (node (ref "D403") (pin "K") (pinfunction "C_K") (pintype "passive"))
      (node (ref "K403") (pin "3") (pinfunction "A_3") (pintype "passive"))
    )
    (net (code "38") (name "Net-(D403-PadA)") (class "Default")
      (node (ref "D403") (pin "A") (pinfunction "A_A") (pintype "passive"))
      (node (ref "R403") (pin "2") (pinfunction "2_2") (pintype "passive"))
    )
    (net (code "39") (name "Net-(D404-C)") (class "Default")
      (node (ref "D404") (pin "K") (pinfunction "C_K") (pintype "passive"))
      (node (ref "K404") (pin "3") (pinfunction "A_3") (pintype "passive"))
    )
    (net (code "40") (name "Net-(D404-PadA)") (class "Default")
      (node (ref "D404") (pin "A") (pinfunction "A_A") (pintype "passive"))
      (node (ref "R404") (pin "2") (pinfunction "2_2") (pintype "passive"))
    )
    (net (code "41") (name "Net-(D405-C)") (class "Default")
      (node (ref "D405") (pin "K") (pinfunction "C_K") (pintype "passive"))
      (node (ref "K405") (pin "3") (pinfunction "A_3") (pintype "passive"))
    )
    (net (code "42") (name "Net-(D405-PadA)") (class "Default")
      (node (ref "D405") (pin "A") (pinfunction "A_A") (pintype "passive"))
      (node (ref "R405") (pin "2") (pinfunction "2_2") (pintype "passive"))
    )
    (net (code "43") (name "Net-(D406-C)") (class "Default")
      (node (ref "D406") (pin "K") (pinfunction "C_K") (pintype "passive"))
      (node (ref "K406") (pin "3") (pinfunction "A_3") (pintype "passive"))
    )
    (net (code "44") (name "Net-(D406-PadA)") (class "Default")
      (node (ref "D406") (pin "A") (pinfunction "A_A") (pintype "passive"))
      (node (ref "R406") (pin "2") (pinfunction "2_2") (pintype "passive"))
    )
    (net (code "45") (name "Net-(D407-C)") (class "Default")
      (node (ref "D407") (pin "K") (pinfunction "C_K") (pintype "passive"))
      (node (ref "K407") (pin "3") (pinfunction "A_3") (pintype "passive"))
    )
    (net (code "46") (name "Net-(D407-PadA)") (class "Default")
      (node (ref "D407") (pin "A") (pinfunction "A_A") (pintype "passive"))
      (node (ref "R407") (pin "2") (pinfunction "2_2") (pintype "passive"))
    )
    (net (code "47") (name "Net-(D408-C)") (class "Default")
      (node (ref "D408") (pin "K") (pinfunction "C_K") (pintype "passive"))
      (node (ref "K408") (pin "3") (pinfunction "A_3") (pintype "passive"))
    )
    (net (code "48") (name "Net-(D408-PadA)") (class "Default")
      (node (ref "D408") (pin "A") (pinfunction "A_A") (pintype "passive"))
      (node (ref "R408") (pin "2") (pinfunction "2_2") (pintype "passive"))
    )
    (net (code "49") (name "Net-(G101-+VIN)") (class "Default")
      (node (ref "D101") (pin "K") (pinfunction "K_K") (pintype "passive"))
      (node (ref "G101") (pin "2") (pinfunction "+VIN_2") (pintype "passive"))
    )
    (net (code "50") (name "Net-(G101-+VOUT)") (class "Default")
      (node (ref "F101") (pin "2") (pinfunction "2_2") (pintype "passive"))
      (node (ref "G101") (pin "4") (pinfunction "+VOUT_4") (pintype "passive"))
    )
    (net (code "51") (name "Net-(G101--VIN)") (class "Default")
      (node (ref "G101") (pin "1") (pinfunction "-VIN_1") (pintype "passive"))
      (node (ref "X101") (pin "2") (pinfunction "A_2") (pintype "passive"))
    )
    (net (code "52") (name "Net-(IC201-(ADC0)PA0)") (class "Default")
      (node (ref "IC201") (pin "37") (pinfunction "(ADC0)PA0_37") (pintype "bidirectional"))
      (node (ref "R202") (pin "2") (pinfunction "2_2") (pintype "passive"))
    )
    (net (code "53") (name "Net-(IC201-(ADC1)PA1)") (class "Default")
      (node (ref "IC201") (pin "36") (pinfunction "(ADC1)PA1_36") (pintype "bidirectional"))
      (node (ref "R203") (pin "2") (pinfunction "2_2") (pintype "passive"))
    )
    (net (code "54") (name "Net-(IC201-(ADC7)PA7)") (class "Default")
      (node (ref "IC201") (pin "30") (pinfunction "(ADC7)PA7_30") (pintype "bidirectional"))
      (node (ref "R204") (pin "1") (pinfunction "1_1") (pintype "passive"))
      (node (ref "R205") (pin "1") (pinfunction "1_1") (pintype "passive"))
    )
    (net (code "55") (name "Net-(IC201-AREF)") (class "Default")
      (node (ref "C205") (pin "1") (pinfunction "1_1") (pintype "passive"))
      (node (ref "IC201") (pin "29") (pinfunction "AREF_29") (pintype "passive"))
    )
    (net (code "56") (name "Net-(IC201-RESET)") (class "Default")
      (node (ref "IC201") (pin "4") (pinfunction "RESET_4") (pintype "input"))
      (node (ref "R201") (pin "1") (pinfunction "1_1") (pintype "passive"))
      (node (ref "X201") (pin "RESET") (pinfunction "RESET_RESET") (pintype "passive"))
    )
    (net (code "57") (name "Net-(IC202A-X1)") (class "Default")
      (node (ref "IC202") (pin "1") (pinfunction "X1_1") (pintype "bidirectional"))
      (node (ref "Q201") (pin "2") (pinfunction "2_2") (pintype "passive"))
    )
    (net (code "58") (name "Net-(IC202A-X2)") (class "Default")
      (node (ref "IC202") (pin "2") (pinfunction "X2_2") (pintype "bidirectional"))
      (node (ref "Q201") (pin "1") (pinfunction "1_1") (pintype "passive"))
    )
    (net (code "59") (name "Net-(IC202B-VCC)") (class "Default")
      (node (ref "C104") (pin "1") (pinfunction "1_1") (pintype "passive"))
      (node (ref "D103") (pin "K") (pinfunction "K_K") (pintype "passive"))
      (node (ref "D104") (pin "K") (pinfunction "K_K") (pintype "passive"))
      (node (ref "IC202") (pin "8") (pinfunction "VCC_8") (pintype "power_in"))
    )
    (net (code "60") (name "Net-(IC203A-A)") (class "Default")
      (node (ref "IC203") (pin "6") (pinfunction "A_6") (pintype "passive"))
      (node (ref "S201") (pin "84") (pinfunction "4_84") (pintype "passive"))
      (node (ref "X202") (pin "1") (pinfunction "A_1") (pintype "passive"))
    )
    (net (code "61") (name "Net-(IC203A-B)") (class "Default")
      (node (ref "IC203") (pin "7") (pinfunction "B_7") (pintype "passive"))
      (node (ref "R206") (pin "1") (pinfunction "1_1") (pintype "passive"))
      (node (ref "X202") (pin "2") (pinfunction "A_2") (pintype "passive"))
    )
    (net (code "62") (name "Net-(IC204A-A)") (class "Default")
      (node (ref "IC204") (pin "2") (pinfunction "A_2") (pintype "input"))
      (node (ref "R207") (pin "2") (pinfunction "2_2") (pintype "passive"))
      (node (ref "S201") (pin "13") (pinfunction "3_13") (pintype "passive"))
    )
    (net (code "63") (name "Net-(IC204A-B)") (class "Default")
      (node (ref "IC204") (pin "3") (pinfunction "B_3") (pintype "input"))
      (node (ref "R208") (pin "2") (pinfunction "2_2") (pintype "passive"))
      (node (ref "S201") (pin "23") (pinfunction "3_23") (pintype "passive"))
    )
    (net (code "64") (name "Net-(IC204A-C)") (class "Default")
      (node (ref "IC204") (pin "4") (pinfunction "C_4") (pintype "input"))
      (node (ref "R209") (pin "2") (pinfunction "2_2") (pintype "passive"))
      (node (ref "S201") (pin "33") (pinfunction "3_33") (pintype "passive"))
    )
    (net (code "65") (name "Net-(IC204A-D)") (class "Default")
      (node (ref "IC204") (pin "5") (pinfunction "D_5") (pintype "input"))
      (node (ref "R210") (pin "2") (pinfunction "2_2") (pintype "passive"))
      (node (ref "S201") (pin "43") (pinfunction "3_43") (pintype "passive"))
    )
    (net (code "66") (name "Net-(IC204A-E)") (class "Default")
      (node (ref "IC204") (pin "10") (pinfunction "E_10") (pintype "input"))
      (node (ref "R211") (pin "2") (pinfunction "2_2") (pintype "passive"))
      (node (ref "S201") (pin "53") (pinfunction "3_53") (pintype "passive"))
    )
    (net (code "67") (name "Net-(IC204A-F)") (class "Default")
      (node (ref "IC204") (pin "11") (pinfunction "F_11") (pintype "input"))
      (node (ref "R212") (pin "2") (pinfunction "2_2") (pintype "passive"))
      (node (ref "S201") (pin "63") (pinfunction "3_63") (pintype "passive"))
    )
    (net (code "68") (name "Net-(IC204A-G)") (class "Default")
      (node (ref "IC204") (pin "12") (pinfunction "G_12") (pintype "input"))
      (node (ref "R213") (pin "2") (pinfunction "2_2") (pintype "passive"))
      (node (ref "S201") (pin "73") (pinfunction "3_73") (pintype "passive"))
    )
    (net (code "69") (name "Net-(IC301-A)") (class "Default")
      (node (ref "IC301") (pin "1") (pinfunction "A_1") (pintype "passive"))
      (node (ref "R309") (pin "1") (pinfunction "1_1") (pintype "passive"))
    )
    (net (code "70") (name "Net-(IC301-C)") (class "Default")
      (node (ref "IC301") (pin "4") (pinfunction "C_4") (pintype "passive"))
      (node (ref "T301") (pin "1") (pinfunction "B_1") (pintype "passive"))
    )
    (net (code "71") (name "Net-(IC301-K)") (class "Default")
      (node (ref "IC301") (pin "2") (pinfunction "K_2") (pintype "passive"))
      (node (ref "R317") (pin "2") (pinfunction "2_2") (pintype "passive"))
    )
    (net (code "72") (name "Net-(IC302-A)") (class "Default")
      (node (ref "IC302") (pin "1") (pinfunction "A_1") (pintype "passive"))
      (node (ref "R310") (pin "1") (pinfunction "1_1") (pintype "passive"))
    )
    (net (code "73") (name "Net-(IC302-C)") (class "Default")
      (node (ref "IC302") (pin "4") (pinfunction "C_4") (pintype "passive"))
      (node (ref "T302") (pin "1") (pinfunction "B_1") (pintype "passive"))
    )
    (net (code "74") (name "Net-(IC302-K)") (class "Default")
      (node (ref "IC302") (pin "2") (pinfunction "K_2") (pintype "passive"))
      (node (ref "R318") (pin "2") (pinfunction "2_2") (pintype "passive"))
    )
    (net (code "75") (name "Net-(IC303-A)") (class "Default")
      (node (ref "IC303") (pin "1") (pinfunction "A_1") (pintype "passive"))
      (node (ref "R311") (pin "1") (pinfunction "1_1") (pintype "passive"))
    )
    (net (code "76") (name "Net-(IC303-C)") (class "Default")
      (node (ref "IC303") (pin "4") (pinfunction "C_4") (pintype "passive"))
      (node (ref "T303") (pin "1") (pinfunction "B_1") (pintype "passive"))
    )
    (net (code "77") (name "Net-(IC303-K)") (class "Default")
      (node (ref "IC303") (pin "2") (pinfunction "K_2") (pintype "passive"))
      (node (ref "R319") (pin "2") (pinfunction "2_2") (pintype "passive"))
    )
    (net (code "78") (name "Net-(IC304-A)") (class "Default")
      (node (ref "IC304") (pin "1") (pinfunction "A_1") (pintype "passive"))
      (node (ref "R312") (pin "1") (pinfunction "1_1") (pintype "passive"))
    )
    (net (code "79") (name "Net-(IC304-C)") (class "Default")
      (node (ref "IC304") (pin "4") (pinfunction "C_4") (pintype "passive"))
      (node (ref "T304") (pin "1") (pinfunction "B_1") (pintype "passive"))
    )
    (net (code "80") (name "Net-(IC304-K)") (class "Default")
      (node (ref "IC304") (pin "2") (pinfunction "K_2") (pintype "passive"))
      (node (ref "R320") (pin "2") (pinfunction "2_2") (pintype "passive"))
    )
    (net (code "81") (name "Net-(IC305-A)") (class "Default")
      (node (ref "IC305") (pin "1") (pinfunction "A_1") (pintype "passive"))
      (node (ref "R313") (pin "1") (pinfunction "1_1") (pintype "passive"))
    )
    (net (code "82") (name "Net-(IC305-C)") (class "Default")
      (node (ref "IC305") (pin "4") (pinfunction "C_4") (pintype "passive"))
      (node (ref "T305") (pin "1") (pinfunction "B_1") (pintype "passive"))
    )
    (net (code "83") (name "Net-(IC305-K)") (class "Default")
      (node (ref "IC305") (pin "2") (pinfunction "K_2") (pintype "passive"))
      (node (ref "R321") (pin "2") (pinfunction "2_2") (pintype "passive"))
    )
    (net (code "84") (name "Net-(IC306-A)") (class "Default")
      (node (ref "IC306") (pin "1") (pinfunction "A_1") (pintype "passive"))
      (node (ref "R314") (pin "1") (pinfunction "1_1") (pintype "passive"))
    )
    (net (code "85") (name "Net-(IC306-C)") (class "Default")
      (node (ref "IC306") (pin "4") (pinfunction "C_4") (pintype "passive"))
      (node (ref "T306") (pin "1") (pinfunction "B_1") (pintype "passive"))
    )
    (net (code "86") (name "Net-(IC306-K)") (class "Default")
      (node (ref "IC306") (pin "2") (pinfunction "K_2") (pintype "passive"))
      (node (ref "R322") (pin "2") (pinfunction "2_2") (pintype "passive"))
    )
    (net (code "87") (name "Net-(IC307-A)") (class "Default")
      (node (ref "IC307") (pin "1") (pinfunction "A_1") (pintype "passive"))
      (node (ref "R315") (pin "1") (pinfunction "1_1") (pintype "passive"))
    )
    (net (code "88") (name "Net-(IC307-C)") (class "Default")
      (node (ref "IC307") (pin "4") (pinfunction "C_4") (pintype "passive"))
      (node (ref "T307") (pin "1") (pinfunction "B_1") (pintype "passive"))
    )
    (net (code "89") (name "Net-(IC307-K)") (class "Default")
      (node (ref "IC307") (pin "2") (pinfunction "K_2") (pintype "passive"))
      (node (ref "R323") (pin "2") (pinfunction "2_2") (pintype "passive"))
    )
    (net (code "90") (name "Net-(IC308-A)") (class "Default")
      (node (ref "IC308") (pin "1") (pinfunction "A_1") (pintype "passive"))
      (node (ref "R316") (pin "1") (pinfunction "1_1") (pintype "passive"))
    )
    (net (code "91") (name "Net-(IC308-C)") (class "Default")
      (node (ref "IC308") (pin "4") (pinfunction "C_4") (pintype "passive"))
      (node (ref "T308") (pin "1") (pinfunction "B_1") (pintype "passive"))
    )
    (net (code "92") (name "Net-(IC308-K)") (class "Default")
      (node (ref "IC308") (pin "2") (pinfunction "K_2") (pintype "passive"))
      (node (ref "R324") (pin "2") (pinfunction "2_2") (pintype "passive"))
    )
    (net (code "93") (name "Net-(IC401A-QA)") (class "Default")
      (node (ref "IC401") (pin "15") (pinfunction "QA_15") (pintype "tri_state"))
      (node (ref "R401") (pin "1") (pinfunction "1_1") (pintype "passive"))
    )
    (net (code "94") (name "Net-(IC401A-QB)") (class "Default")
      (node (ref "IC401") (pin "1") (pinfunction "QB_1") (pintype "tri_state"))
      (node (ref "R402") (pin "1") (pinfunction "1_1") (pintype "passive"))
    )
    (net (code "95") (name "Net-(IC401A-QC)") (class "Default")
      (node (ref "IC401") (pin "2") (pinfunction "QC_2") (pintype "tri_state"))
      (node (ref "R403") (pin "1") (pinfunction "1_1") (pintype "passive"))
    )
    (net (code "96") (name "Net-(IC401A-QD)") (class "Default")
      (node (ref "IC401") (pin "3") (pinfunction "QD_3") (pintype "tri_state"))
      (node (ref "R404") (pin "1") (pinfunction "1_1") (pintype "passive"))
    )
    (net (code "97") (name "Net-(IC401A-QE)") (class "Default")
      (node (ref "IC401") (pin "4") (pinfunction "QE_4") (pintype "tri_state"))
      (node (ref "R405") (pin "1") (pinfunction "1_1") (pintype "passive"))
    )
    (net (code "98") (name "Net-(IC401A-QF)") (class "Default")
      (node (ref "IC401") (pin "5") (pinfunction "QF_5") (pintype "tri_state"))
      (node (ref "R406") (pin "1") (pinfunction "1_1") (pintype "passive"))
    )
    (net (code "99") (name "Net-(IC401A-QG)") (class "Default")
      (node (ref "IC401") (pin "6") (pinfunction "QG_6") (pintype "tri_state"))
      (node (ref "R407") (pin "1") (pinfunction "1_1") (pintype "passive"))
    )
    (net (code "100") (name "Net-(IC401A-QH)") (class "Default")
      (node (ref "IC401") (pin "7") (pinfunction "QH_7") (pintype "tri_state"))
      (node (ref "R408") (pin "1") (pinfunction "1_1") (pintype "passive"))
    )
    (net (code "101") (name "Net-(K401-DS1)") (class "Default")
      (node (ref "K401") (pin "1") (pinfunction "DS1_1") (pintype "passive"))
      (node (ref "X402") (pin "1") (pinfunction "A_1") (pintype "passive"))
    )
    (net (code "102") (name "Net-(K401-DS2)") (class "Default")
      (node (ref "K401") (pin "2") (pinfunction "DS2_2") (pintype "passive"))
      (node (ref "K402") (pin "2") (pinfunction "DS2_2") (pintype "passive"))
      (node (ref "K403") (pin "2") (pinfunction "DS2_2") (pintype "passive"))
      (node (ref "K404") (pin "2") (pinfunction "DS2_2") (pintype "passive"))
      (node (ref "K405") (pin "2") (pinfunction "DS2_2") (pintype "passive"))
      (node (ref "K406") (pin "2") (pinfunction "DS2_2") (pintype "passive"))
      (node (ref "K407") (pin "2") (pinfunction "DS2_2") (pintype "passive"))
      (node (ref "K408") (pin "2") (pinfunction "DS2_2") (pintype "passive"))
      (node (ref "X401") (pin "1") (pinfunction "A_1") (pintype "passive"))
      (node (ref "X401") (pin "2") (pinfunction "A_2") (pintype "passive"))
    )
    (net (code "103") (name "Net-(K402-DS1)") (class "Default")
      (node (ref "K402") (pin "1") (pinfunction "DS1_1") (pintype "passive"))
      (node (ref "X402") (pin "2") (pinfunction "A_2") (pintype "passive"))
    )
    (net (code "104") (name "Net-(K403-DS1)") (class "Default")
      (node (ref "K403") (pin "1") (pinfunction "DS1_1") (pintype "passive"))
      (node (ref "X403") (pin "1") (pinfunction "A_1") (pintype "passive"))
    )
    (net (code "105") (name "Net-(K404-DS1)") (class "Default")
      (node (ref "K404") (pin "1") (pinfunction "DS1_1") (pintype "passive"))
      (node (ref "X403") (pin "2") (pinfunction "A_2") (pintype "passive"))
    )
    (net (code "106") (name "Net-(K405-DS1)") (class "Default")
      (node (ref "K405") (pin "1") (pinfunction "DS1_1") (pintype "passive"))
      (node (ref "X404") (pin "1") (pinfunction "A_1") (pintype "passive"))
    )
    (net (code "107") (name "Net-(K406-DS1)") (class "Default")
      (node (ref "K406") (pin "1") (pinfunction "DS1_1") (pintype "passive"))
      (node (ref "X404") (pin "2") (pinfunction "A_2") (pintype "passive"))
    )
    (net (code "108") (name "Net-(K407-DS1)") (class "Default")
      (node (ref "K407") (pin "1") (pinfunction "DS1_1") (pintype "passive"))
      (node (ref "X405") (pin "1") (pinfunction "A_1") (pintype "passive"))
    )
    (net (code "109") (name "Net-(K408-DS1)") (class "Default")
      (node (ref "K408") (pin "1") (pinfunction "DS1_1") (pintype "passive"))
      (node (ref "X405") (pin "2") (pinfunction "A_2") (pintype "passive"))
    )
    (net (code "110") (name "Net-(S201H-3)") (class "Default")
      (node (ref "R206") (pin "2") (pinfunction "2_2") (pintype "passive"))
      (node (ref "S201") (pin "83") (pinfunction "3_83") (pintype "passive"))
    )
    (net (code "111") (name "Net-(X101A-A)") (class "Default")
      (node (ref "D101") (pin "A") (pinfunction "A_A") (pintype "passive"))
      (node (ref "X101") (pin "1") (pinfunction "A_1") (pintype "passive"))
    )
    (net (code "112") (name "Net-(X302A-A)") (class "Default")
      (node (ref "R310") (pin "2") (pinfunction "2_2") (pintype "passive"))
      (node (ref "X302") (pin "1") (pinfunction "A_1") (pintype "passive"))
    )
    (net (code "113") (name "Net-(X302B-A)") (class "Default")
      (node (ref "R309") (pin "2") (pinfunction "2_2") (pintype "passive"))
      (node (ref "X302") (pin "2") (pinfunction "A_2") (pintype "passive"))
    )
    (net (code "114") (name "Net-(X303A-A)") (class "Default")
      (node (ref "R312") (pin "2") (pinfunction "2_2") (pintype "passive"))
      (node (ref "X303") (pin "1") (pinfunction "A_1") (pintype "passive"))
    )
    (net (code "115") (name "Net-(X303B-A)") (class "Default")
      (node (ref "R311") (pin "2") (pinfunction "2_2") (pintype "passive"))
      (node (ref "X303") (pin "2") (pinfunction "A_2") (pintype "passive"))
    )
    (net (code "116") (name "Net-(X304A-A)") (class "Default")
      (node (ref "R314") (pin "2") (pinfunction "2_2") (pintype "passive"))
      (node (ref "X304") (pin "1") (pinfunction "A_1") (pintype "passive"))
    )
    (net (code "117") (name "Net-(X304B-A)") (class "Default")
      (node (ref "R313") (pin "2") (pinfunction "2_2") (pintype "passive"))
      (node (ref "X304") (pin "2") (pinfunction "A_2") (pintype "passive"))
    )
    (net (code "118") (name "Net-(X305A-A)") (class "Default")
      (node (ref "R316") (pin "2") (pinfunction "2_2") (pintype "passive"))
      (node (ref "X305") (pin "1") (pinfunction "A_1") (pintype "passive"))
    )
    (net (code "119") (name "Net-(X305B-A)") (class "Default")
      (node (ref "R315") (pin "2") (pinfunction "2_2") (pintype "passive"))
      (node (ref "X305") (pin "2") (pinfunction "A_2") (pintype "passive"))
    )
    (net (code "120") (name "RE") (class "Default")
      (node (ref "IC201") (pin "14") (pinfunction "(OC1A)PD5_14") (pintype "bidirectional"))
      (node (ref "IC203") (pin "2") (pinfunction "RE/_2") (pintype "input"))
    )
    (net (code "121") (name "RXD") (class "Default")
      (node (ref "IC201") (pin "9") (pinfunction "(RXD)PD0_9") (pintype "bidirectional"))
      (node (ref "IC203") (pin "1") (pinfunction "RO_1") (pintype "output"))
    )
    (net (code "122") (name "SCK") (class "Default")
      (node (ref "IC201") (pin "3") (pinfunction "(SCK)PB7_3") (pintype "bidirectional"))
      (node (ref "X201") (pin "SCK") (pinfunction "SCK_SCK") (pintype "passive"))
    )
    (net (code "123") (name "SCL") (class "Default")
      (node (ref "IC201") (pin "15") (pinfunction "(ICP)PD6_15") (pintype "bidirectional"))
      (node (ref "IC202") (pin "6") (pinfunction "SCL_6") (pintype "bidirectional"))
    )
    (net (code "124") (name "SDA") (class "Default")
      (node (ref "IC201") (pin "16") (pinfunction "(OC2)PD7_16") (pintype "bidirectional"))
      (node (ref "IC202") (pin "5") (pinfunction "SDA_5") (pintype "bidirectional"))
    )
    (net (code "125") (name "TE") (class "Default")
      (node (ref "IC201") (pin "13") (pinfunction "(OC1B)PD4_13") (pintype "bidirectional"))
      (node (ref "IC203") (pin "3") (pinfunction "DE_3") (pintype "input"))
    )
    (net (code "126") (name "TXD") (class "Default")
      (node (ref "IC201") (pin "10") (pinfunction "(TXD)PD1_10") (pintype "bidirectional"))
      (node (ref "IC203") (pin "4") (pinfunction "DI_4") (pintype "input"))
    )
    (net (code "127") (name "unconnected-(IC201-(ADC2)PA2-Pad35)") (class "Default")
      (node (ref "IC201") (pin "35") (pinfunction "(ADC2)PA2_35") (pintype "bidirectional"))
    )
    (net (code "128") (name "unconnected-(IC201-(ADC3)PA3-Pad34)") (class "Default")
      (node (ref "IC201") (pin "34") (pinfunction "(ADC3)PA3_34") (pintype "bidirectional"))
    )
    (net (code "129") (name "unconnected-(IC201-(ADC4)PA4-Pad33)") (class "Default")
      (node (ref "IC201") (pin "33") (pinfunction "(ADC4)PA4_33") (pintype "bidirectional"))
    )
    (net (code "130") (name "unconnected-(IC201-(ADC5)PA5-Pad32)") (class "Default")
      (node (ref "IC201") (pin "32") (pinfunction "(ADC5)PA5_32") (pintype "bidirectional"))
    )
    (net (code "131") (name "unconnected-(IC201-XTAL1-Pad8)") (class "Default")
      (node (ref "IC201") (pin "8") (pinfunction "XTAL1_8") (pintype "bidirectional"))
    )
    (net (code "132") (name "unconnected-(IC201-XTAL2-Pad7)") (class "Default")
      (node (ref "IC201") (pin "7") (pinfunction "XTAL2_7") (pintype "bidirectional"))
    )
    (net (code "133") (name "unconnected-(IC401A-QH*-Pad9)") (class "Default")
      (node (ref "IC401") (pin "9") (pinfunction "QH*_9") (pintype "tri_state"))
    )
    (net (code "134") (name "~{R}") (class "Default")
      (node (ref "IC201") (pin "40") (pinfunction "(T0/XCK)PB0_40") (pintype "bidirectional"))
      (node (ref "IC204") (pin "9") (pinfunction "~{CLR}_9") (pintype "input"))
      (node (ref "IC401") (pin "10") (pinfunction "~{SCLR}_10") (pintype "input"))
    )
  )
)
